# LM35.net
KiCad netlist of a schematic drawn in Altium Designer
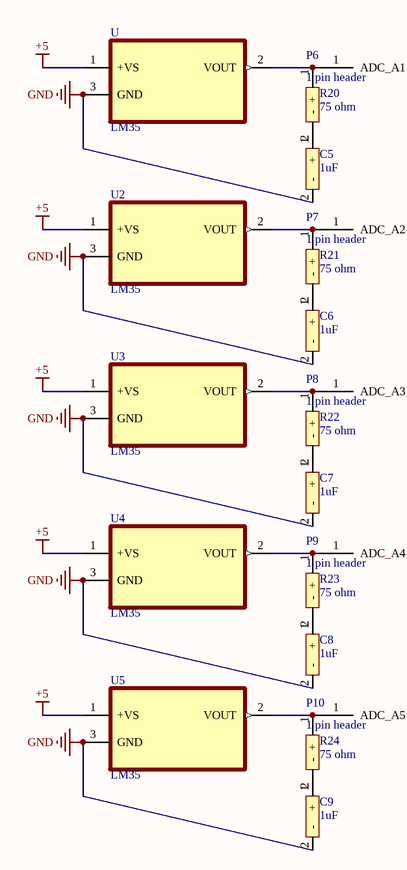
[diagram p0: LM35.SchDoc]

(export (version "E")
  (design (tool "Eeschema 10.0.6"))
  (components
    (comp (ref "C5")
      (value "1uF")
      (footprint "10NF_KUTUPSUZ")
      (libsource (lib "Schlib1") (part "10nf_kutupsuz"))
    )
    (comp (ref "C6")
      (value "1uF")
      (footprint "10NF_KUTUPSUZ")
      (libsource (lib "Schlib1") (part "10nf_kutupsuz"))
    )
    (comp (ref "C7")
      (value "1uF")
      (footprint "10NF_KUTUPSUZ")
      (libsource (lib "Schlib1") (part "10nf_kutupsuz"))
    )
    (comp (ref "C8")
      (value "1uF")
      (footprint "10NF_KUTUPSUZ")
      (libsource (lib "Schlib1") (part "10nf_kutupsuz"))
    )
    (comp (ref "C9")
      (value "1uF")
      (footprint "10NF_KUTUPSUZ")
      (libsource (lib "Schlib1") (part "10nf_kutupsuz"))
    )
    (comp (ref "P6")
      (value "1 pin header")
      (footprint "1pinheader")
      (libsource (lib "Schlib1") (part "1 pin header"))
    )
    (comp (ref "P7")
      (value "1 pin header")
      (footprint "1pinheader")
      (libsource (lib "Schlib1") (part "1 pin header"))
    )
    (comp (ref "P8")
      (value "1 pin header")
      (footprint "1pinheader")
      (libsource (lib "Schlib1") (part "1 pin header"))
    )
    (comp (ref "P9")
      (value "1 pin header")
      (footprint "1pinheader")
      (libsource (lib "Schlib1") (part "1 pin header"))
    )
    (comp (ref "P10")
      (value "1 pin header")
      (footprint "1pinheader")
      (libsource (lib "Schlib1") (part "1 pin header"))
    )
    (comp (ref "R20")
      (value "75 ohm")
      (footprint "100 resistor")
      (libsource (lib "Schlib1") (part "100 resistor"))
    )
    (comp (ref "R21")
      (value "75 ohm")
      (footprint "100 resistor")
      (libsource (lib "Schlib1") (part "100 resistor"))
    )
    (comp (ref "R22")
      (value "75 ohm")
      (footprint "100 resistor")
      (libsource (lib "Schlib1") (part "100 resistor"))
    )
    (comp (ref "R23")
      (value "75 ohm")
      (footprint "100 resistor")
      (libsource (lib "Schlib1") (part "100 resistor"))
    )
    (comp (ref "R24")
      (value "75 ohm")
      (footprint "100 resistor")
      (libsource (lib "Schlib1") (part "100 resistor"))
    )
    (comp (ref "U")
      (value "LM35")
      (footprint "TO127P254X495-3P:TO127P254X495-3P")
      (fields
        (field (name "MF") "Texas Instruments")
        (field (name "MP") "LM35DZ/LFT4")
        (field (name "BUYPART") "https://www.snapeda.com/parts/LM35DZ/LFT4/Texas%20Instruments/view-part/19434/?ref=eda")
      )
      (libsource (lib "Schlib1") (part "LM35DZ/LFT4"))
    )
    (comp (ref "U2")
      (value "LM35")
      (footprint "TO127P254X495-3P:TO127P254X495-3P")
      (fields
        (field (name "MF") "Texas Instruments")
        (field (name "MP") "LM35DZ/LFT4")
        (field (name "BUYPART") "https://www.snapeda.com/parts/LM35DZ/LFT4/Texas%20Instruments/view-part/19434/?ref=eda")
      )
      (libsource (lib "Schlib1") (part "LM35DZ/LFT4"))
    )
    (comp (ref "U3")
      (value "LM35")
      (footprint "TO127P254X495-3P:TO127P254X495-3P")
      (fields
        (field (name "MF") "Texas Instruments")
        (field (name "MP") "LM35DZ/LFT4")
        (field (name "BUYPART") "https://www.snapeda.com/parts/LM35DZ/LFT4/Texas%20Instruments/view-part/19434/?ref=eda")
      )
      (libsource (lib "Schlib1") (part "LM35DZ/LFT4"))
    )
    (comp (ref "U4")
      (value "LM35")
      (footprint "TO127P254X495-3P:TO127P254X495-3P")
      (fields
        (field (name "MF") "Texas Instruments")
        (field (name "MP") "LM35DZ/LFT4")
        (field (name "BUYPART") "https://www.snapeda.com/parts/LM35DZ/LFT4/Texas%20Instruments/view-part/19434/?ref=eda")
      )
      (libsource (lib "Schlib1") (part "LM35DZ/LFT4"))
    )
    (comp (ref "U5")
      (value "LM35")
      (footprint "TO127P254X495-3P:TO127P254X495-3P")
      (fields
        (field (name "MF") "Texas Instruments")
        (field (name "MP") "LM35DZ/LFT4")
        (field (name "BUYPART") "https://www.snapeda.com/parts/LM35DZ/LFT4/Texas%20Instruments/view-part/19434/?ref=eda")
      )
      (libsource (lib "Schlib1") (part "LM35DZ/LFT4"))
    )
  )
  (nets
    (net (code "1") (name "+5") (class "Default")
      (node (ref "U") (pin "1") (pinfunction "+VS_1") (pintype "power_in"))
      (node (ref "U2") (pin "1") (pinfunction "+VS_1") (pintype "power_in"))
      (node (ref "U3") (pin "1") (pinfunction "+VS_1") (pintype "power_in"))
      (node (ref "U4") (pin "1") (pinfunction "+VS_1") (pintype "power_in"))
      (node (ref "U5") (pin "1") (pinfunction "+VS_1") (pintype "power_in"))
    )
    (net (code "2") (name "GND") (class "Default")
      (node (ref "C5") (pin "2") (pinfunction "-_2") (pintype "passive"))
      (node (ref "C6") (pin "2") (pinfunction "-_2") (pintype "passive"))
      (node (ref "C7") (pin "2") (pinfunction "-_2") (pintype "passive"))
      (node (ref "C8") (pin "2") (pinfunction "-_2") (pintype "passive"))
      (node (ref "C9") (pin "2") (pinfunction "-_2") (pintype "passive"))
      (node (ref "U") (pin "3") (pinfunction "GND_3") (pintype "passive"))
      (node (ref "U2") (pin "3") (pinfunction "GND_3") (pintype "passive"))
      (node (ref "U3") (pin "3") (pinfunction "GND_3") (pintype "passive"))
      (node (ref "U4") (pin "3") (pinfunction "GND_3") (pintype "passive"))
      (node (ref "U5") (pin "3") (pinfunction "GND_3") (pintype "passive"))
    )
    (net (code "3") (name "Net-(P6-ADC_A1)") (class "Default")
      (node (ref "P6") (pin "1") (pinfunction "ADC_A1_1") (pintype "passive"))
      (node (ref "R20") (pin "1") (pinfunction "+_1") (pintype "passive"))
      (node (ref "U") (pin "2") (pinfunction "VOUT_2") (pintype "output"))
    )
    (net (code "4") (name "Net-(P7-ADC_A1)") (class "Default")
      (node (ref "P7") (pin "1") (pinfunction "ADC_A1_1") (pintype "passive"))
      (node (ref "R21") (pin "1") (pinfunction "+_1") (pintype "passive"))
      (node (ref "U2") (pin "2") (pinfunction "VOUT_2") (pintype "output"))
    )
    (net (code "5") (name "Net-(P8-ADC_A1)") (class "Default")
      (node (ref "P8") (pin "1") (pinfunction "ADC_A1_1") (pintype "passive"))
      (node (ref "R22") (pin "1") (pinfunction "+_1") (pintype "passive"))
      (node (ref "U3") (pin "2") (pinfunction "VOUT_2") (pintype "output"))
    )
    (net (code "6") (name "Net-(P9-ADC_A1)") (class "Default")
      (node (ref "P9") (pin "1") (pinfunction "ADC_A1_1") (pintype "passive"))
      (node (ref "R23") (pin "1") (pinfunction "+_1") (pintype "passive"))
      (node (ref "U4") (pin "2") (pinfunction "VOUT_2") (pintype "output"))
    )
    (net (code "7") (name "Net-(P10-ADC_A1)") (class "Default")
      (node (ref "P10") (pin "1") (pinfunction "ADC_A1_1") (pintype "passive"))
      (node (ref "R24") (pin "1") (pinfunction "+_1") (pintype "passive"))
      (node (ref "U5") (pin "2") (pinfunction "VOUT_2") (pintype "output"))
    )
    (net (code "8") (name "unconnected-(C5-+-Pad1)") (class "Default")
      (node (ref "C5") (pin "1") (pinfunction "+_1") (pintype "passive"))
    )
    (net (code "9") (name "unconnected-(C6-+-Pad1)") (class "Default")
      (node (ref "C6") (pin "1") (pinfunction "+_1") (pintype "passive"))
    )
    (net (code "10") (name "unconnected-(C7-+-Pad1)") (class "Default")
      (node (ref "C7") (pin "1") (pinfunction "+_1") (pintype "passive"))
    )
    (net (code "11") (name "unconnected-(C8-+-Pad1)") (class "Default")
      (node (ref "C8") (pin "1") (pinfunction "+_1") (pintype "passive"))
    )
    (net (code "12") (name "unconnected-(C9-+-Pad1)") (class "Default")
      (node (ref "C9") (pin "1") (pinfunction "+_1") (pintype "passive"))
    )
    (net (code "13") (name "unconnected-(R20---Pad2)") (class "Default")
      (node (ref "R20") (pin "2") (pinfunction "-_2") (pintype "passive"))
    )
    (net (code "14") (name "unconnected-(R21---Pad2)") (class "Default")
      (node (ref "R21") (pin "2") (pinfunction "-_2") (pintype "passive"))
    )
    (net (code "15") (name "unconnected-(R22---Pad2)") (class "Default")
      (node (ref "R22") (pin "2") (pinfunction "-_2") (pintype "passive"))
    )
    (net (code "16") (name "unconnected-(R23---Pad2)") (class "Default")
      (node (ref "R23") (pin "2") (pinfunction "-_2") (pintype "passive"))
    )
    (net (code "17") (name "unconnected-(R24---Pad2)") (class "Default")
      (node (ref "R24") (pin "2") (pinfunction "-_2") (pintype "passive"))
    )
  )
)
